# shield.net
KiCad netlist of a schematic drawn in EAGLE
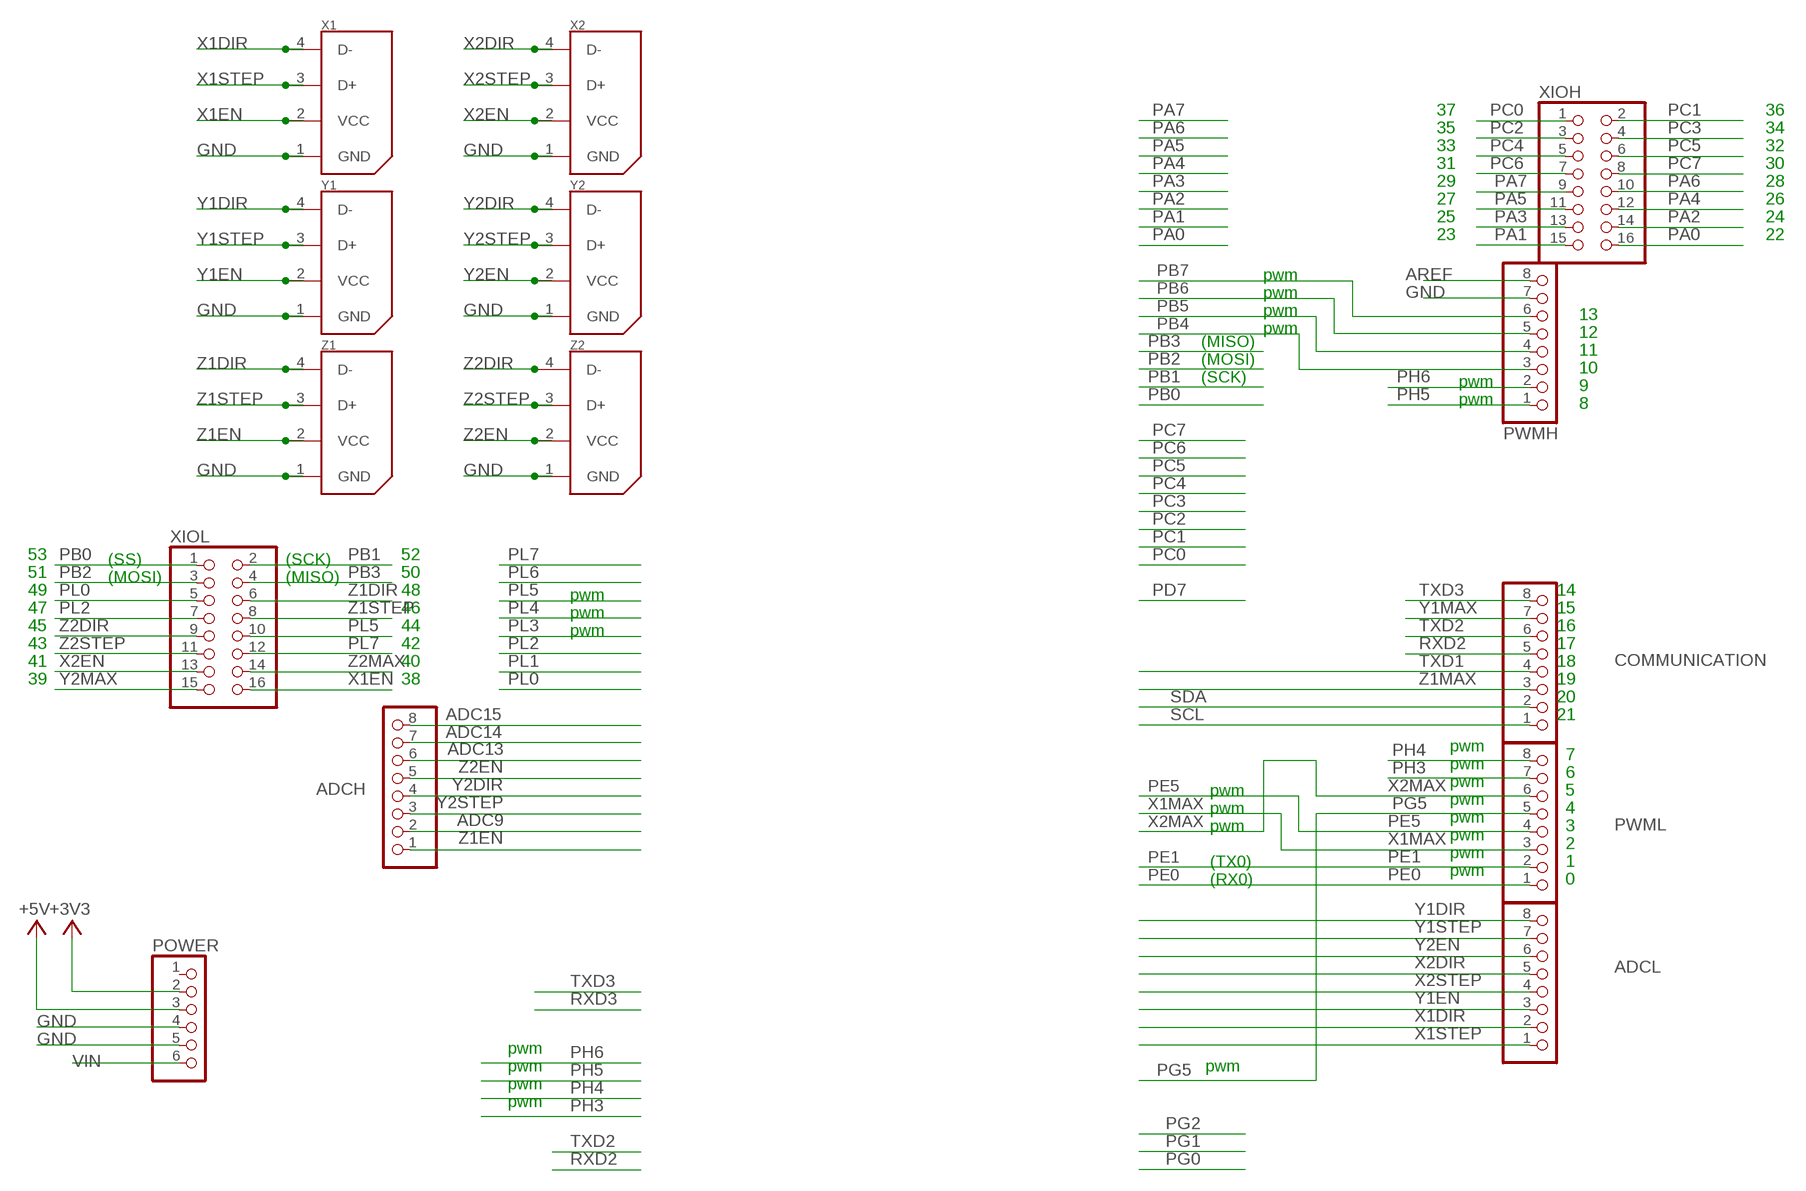
[diagram p0: schematic, sheet 1]

(export (version "E")
  (design (tool "Eeschema 10.0.6"))
  (components
    (comp (ref "ADCH")
      (value "PINHD-1X8")
      (footprint "eagle-import:1X08")
      (libsource (lib "eagle-import") (part "PINHD-1X8"))
    )
    (comp (ref "ADCL")
      (value "PINHD-1X8")
      (footprint "eagle-import:1X08")
      (libsource (lib "eagle-import") (part "PINHD-1X8"))
    )
    (comp (ref "COMMUNICATION")
      (value "PINHD-1X8")
      (footprint "eagle-import:1X08")
      (libsource (lib "eagle-import") (part "PINHD-1X8"))
    )
    (comp (ref "POWER")
      (value "PINHD-1X6")
      (footprint "eagle-import:1X06")
      (libsource (lib "eagle-import") (part "PINHD-1X6"))
    )
    (comp (ref "PWMH")
      (value "PINHD-1X8")
      (footprint "eagle-import:1X08")
      (libsource (lib "eagle-import") (part "PINHD-1X8"))
    )
    (comp (ref "PWML")
      (value "PINHD-1X8")
      (footprint "eagle-import:1X08")
      (libsource (lib "eagle-import") (part "PINHD-1X8"))
    )
    (comp (ref "X1")
      (value "22-03-5045")
      (footprint "eagle-import:5267-4")
      (libsource (lib "eagle-import") (part "22-03-5045"))
    )
    (comp (ref "X2")
      (value "22-03-5045")
      (footprint "eagle-import:5267-4")
      (libsource (lib "eagle-import") (part "22-03-5045"))
    )
    (comp (ref "XIOH")
      (value "PINHD-2X8")
      (footprint "eagle-import:2X08")
      (libsource (lib "eagle-import") (part "PINHD-2X8"))
    )
    (comp (ref "XIOL")
      (value "PINHD-2X8")
      (footprint "eagle-import:2X08")
      (libsource (lib "eagle-import") (part "PINHD-2X8"))
    )
    (comp (ref "Y1")
      (value "22-03-5045")
      (footprint "eagle-import:5267-4")
      (libsource (lib "eagle-import") (part "22-03-5045"))
    )
    (comp (ref "Y2")
      (value "22-03-5045")
      (footprint "eagle-import:5267-4")
      (libsource (lib "eagle-import") (part "22-03-5045"))
    )
    (comp (ref "Z1")
      (value "22-03-5045")
      (footprint "eagle-import:5267-4")
      (libsource (lib "eagle-import") (part "22-03-5045"))
    )
    (comp (ref "Z2")
      (value "22-03-5045")
      (footprint "eagle-import:5267-4")
      (libsource (lib "eagle-import") (part "22-03-5045"))
    )
  )
  (nets
    (net (code "1") (name "+3V3") (class "Default")
      (node (ref "POWER") (pin "2") (pinfunction "2_2") (pintype "passive"))
    )
    (net (code "2") (name "+5V") (class "Default")
      (node (ref "POWER") (pin "3") (pinfunction "3_3") (pintype "passive"))
    )
    (net (code "3") (name "/ADC9") (class "Default")
      (node (ref "ADCH") (pin "2") (pinfunction "2_2") (pintype "passive"))
    )
    (net (code "4") (name "/ADC13") (class "Default")
      (node (ref "ADCH") (pin "6") (pinfunction "6_6") (pintype "passive"))
    )
    (net (code "5") (name "/ADC14") (class "Default")
      (node (ref "ADCH") (pin "7") (pinfunction "7_7") (pintype "passive"))
    )
    (net (code "6") (name "/ADC15") (class "Default")
      (node (ref "ADCH") (pin "8") (pinfunction "8_8") (pintype "passive"))
    )
    (net (code "7") (name "/AREF") (class "Default")
      (node (ref "PWMH") (pin "8") (pinfunction "8_8") (pintype "passive"))
    )
    (net (code "8") (name "/GND") (class "Default")
      (node (ref "POWER") (pin "4") (pinfunction "4_4") (pintype "passive"))
      (node (ref "POWER") (pin "5") (pinfunction "5_5") (pintype "passive"))
      (node (ref "PWMH") (pin "7") (pinfunction "7_7") (pintype "passive"))
      (node (ref "X1") (pin "1") (pinfunction "GND_1") (pintype "bidirectional"))
      (node (ref "X2") (pin "1") (pinfunction "GND_1") (pintype "bidirectional"))
      (node (ref "Y1") (pin "1") (pinfunction "GND_1") (pintype "bidirectional"))
      (node (ref "Y2") (pin "1") (pinfunction "GND_1") (pintype "bidirectional"))
      (node (ref "Z1") (pin "1") (pinfunction "GND_1") (pintype "bidirectional"))
      (node (ref "Z2") (pin "1") (pinfunction "GND_1") (pintype "bidirectional"))
    )
    (net (code "9") (name "/PA0") (class "Default")
      (node (ref "XIOH") (pin "16") (pinfunction "16_16") (pintype "passive"))
    )
    (net (code "10") (name "/PA1") (class "Default")
      (node (ref "XIOH") (pin "15") (pinfunction "15_15") (pintype "passive"))
    )
    (net (code "11") (name "/PA2") (class "Default")
      (node (ref "XIOH") (pin "14") (pinfunction "14_14") (pintype "passive"))
    )
    (net (code "12") (name "/PA3") (class "Default")
      (node (ref "XIOH") (pin "13") (pinfunction "13_13") (pintype "passive"))
    )
    (net (code "13") (name "/PA4") (class "Default")
      (node (ref "XIOH") (pin "12") (pinfunction "12_12") (pintype "passive"))
    )
    (net (code "14") (name "/PA5") (class "Default")
      (node (ref "XIOH") (pin "11") (pinfunction "11_11") (pintype "passive"))
    )
    (net (code "15") (name "/PA6") (class "Default")
      (node (ref "XIOH") (pin "10") (pinfunction "10_10") (pintype "passive"))
    )
    (net (code "16") (name "/PA7") (class "Default")
      (node (ref "XIOH") (pin "9") (pinfunction "9_9") (pintype "passive"))
    )
    (net (code "17") (name "/PB0") (class "Default")
      (node (ref "XIOL") (pin "1") (pinfunction "1_1") (pintype "passive"))
    )
    (net (code "18") (name "/PB1") (class "Default")
      (node (ref "XIOL") (pin "2") (pinfunction "2_2") (pintype "passive"))
    )
    (net (code "19") (name "/PB2") (class "Default")
      (node (ref "XIOL") (pin "3") (pinfunction "3_3") (pintype "passive"))
    )
    (net (code "20") (name "/PB3") (class "Default")
      (node (ref "XIOL") (pin "4") (pinfunction "4_4") (pintype "passive"))
    )
    (net (code "21") (name "/PB4") (class "Default")
      (node (ref "PWMH") (pin "3") (pinfunction "3_3") (pintype "passive"))
    )
    (net (code "22") (name "/PB5") (class "Default")
      (node (ref "PWMH") (pin "4") (pinfunction "4_4") (pintype "passive"))
    )
    (net (code "23") (name "/PB6") (class "Default")
      (node (ref "PWMH") (pin "5") (pinfunction "5_5") (pintype "passive"))
    )
    (net (code "24") (name "/PB7") (class "Default")
      (node (ref "PWMH") (pin "6") (pinfunction "6_6") (pintype "passive"))
    )
    (net (code "25") (name "/PC0") (class "Default")
      (node (ref "XIOH") (pin "1") (pinfunction "1_1") (pintype "passive"))
    )
    (net (code "26") (name "/PC1") (class "Default")
      (node (ref "XIOH") (pin "2") (pinfunction "2_2") (pintype "passive"))
    )
    (net (code "27") (name "/PC2") (class "Default")
      (node (ref "XIOH") (pin "3") (pinfunction "3_3") (pintype "passive"))
    )
    (net (code "28") (name "/PC3") (class "Default")
      (node (ref "XIOH") (pin "4") (pinfunction "4_4") (pintype "passive"))
    )
    (net (code "29") (name "/PC4") (class "Default")
      (node (ref "XIOH") (pin "5") (pinfunction "5_5") (pintype "passive"))
    )
    (net (code "30") (name "/PC5") (class "Default")
      (node (ref "XIOH") (pin "6") (pinfunction "6_6") (pintype "passive"))
    )
    (net (code "31") (name "/PC6") (class "Default")
      (node (ref "XIOH") (pin "7") (pinfunction "7_7") (pintype "passive"))
    )
    (net (code "32") (name "/PC7") (class "Default")
      (node (ref "XIOH") (pin "8") (pinfunction "8_8") (pintype "passive"))
    )
    (net (code "34") (name "/PE0") (class "Default")
      (node (ref "PWML") (pin "1") (pinfunction "1_1") (pintype "passive"))
    )
    (net (code "35") (name "/PE1") (class "Default")
      (node (ref "PWML") (pin "2") (pinfunction "2_2") (pintype "passive"))
    )
    (net (code "36") (name "/PE5") (class "Default")
      (node (ref "PWML") (pin "4") (pinfunction "4_4") (pintype "passive"))
    )
    (net (code "40") (name "/PG5") (class "Default")
      (node (ref "PWML") (pin "5") (pinfunction "5_5") (pintype "passive"))
    )
    (net (code "41") (name "/PH3") (class "Default")
      (node (ref "PWML") (pin "7") (pinfunction "7_7") (pintype "passive"))
    )
    (net (code "42") (name "/PH4") (class "Default")
      (node (ref "PWML") (pin "8") (pinfunction "8_8") (pintype "passive"))
    )
    (net (code "43") (name "/PH5") (class "Default")
      (node (ref "PWMH") (pin "1") (pinfunction "1_1") (pintype "passive"))
    )
    (net (code "44") (name "/PH6") (class "Default")
      (node (ref "PWMH") (pin "2") (pinfunction "2_2") (pintype "passive"))
    )
    (net (code "45") (name "/PL0") (class "Default")
      (node (ref "XIOL") (pin "5") (pinfunction "5_5") (pintype "passive"))
    )
    (net (code "47") (name "/PL2") (class "Default")
      (node (ref "XIOL") (pin "7") (pinfunction "7_7") (pintype "passive"))
    )
    (net (code "50") (name "/PL5") (class "Default")
      (node (ref "XIOL") (pin "10") (pinfunction "10_10") (pintype "passive"))
    )
    (net (code "52") (name "/PL7") (class "Default")
      (node (ref "XIOL") (pin "12") (pinfunction "12_12") (pintype "passive"))
    )
    (net (code "53") (name "/RXD2") (class "Default")
      (node (ref "COMMUNICATION") (pin "5") (pinfunction "5_5") (pintype "passive"))
    )
    (net (code "55") (name "/SCL") (class "Default")
      (node (ref "COMMUNICATION") (pin "1") (pinfunction "1_1") (pintype "passive"))
    )
    (net (code "56") (name "/SDA") (class "Default")
      (node (ref "COMMUNICATION") (pin "2") (pinfunction "2_2") (pintype "passive"))
    )
    (net (code "57") (name "/TXD1") (class "Default")
      (node (ref "COMMUNICATION") (pin "4") (pinfunction "4_4") (pintype "passive"))
    )
    (net (code "58") (name "/TXD2") (class "Default")
      (node (ref "COMMUNICATION") (pin "6") (pinfunction "6_6") (pintype "passive"))
    )
    (net (code "59") (name "/TXD3") (class "Default")
      (node (ref "COMMUNICATION") (pin "8") (pinfunction "8_8") (pintype "passive"))
    )
    (net (code "60") (name "/VIN") (class "Default")
      (node (ref "POWER") (pin "6") (pinfunction "6_6") (pintype "passive"))
    )
    (net (code "61") (name "/X1DIR") (class "Default")
      (node (ref "ADCL") (pin "2") (pinfunction "2_2") (pintype "passive"))
      (node (ref "X1") (pin "4") (pinfunction "D-_4") (pintype "bidirectional"))
    )
    (net (code "62") (name "/X1EN") (class "Default")
      (node (ref "X1") (pin "2") (pinfunction "VCC_2") (pintype "bidirectional"))
      (node (ref "XIOL") (pin "16") (pinfunction "16_16") (pintype "passive"))
    )
    (net (code "63") (name "/X1MAX") (class "Default")
      (node (ref "PWML") (pin "3") (pinfunction "3_3") (pintype "passive"))
    )
    (net (code "64") (name "/X1STEP") (class "Default")
      (node (ref "ADCL") (pin "1") (pinfunction "1_1") (pintype "passive"))
      (node (ref "X1") (pin "3") (pinfunction "D+_3") (pintype "bidirectional"))
    )
    (net (code "65") (name "/X2DIR") (class "Default")
      (node (ref "ADCL") (pin "5") (pinfunction "5_5") (pintype "passive"))
      (node (ref "X2") (pin "4") (pinfunction "D-_4") (pintype "bidirectional"))
    )
    (net (code "66") (name "/X2EN") (class "Default")
      (node (ref "X2") (pin "2") (pinfunction "VCC_2") (pintype "bidirectional"))
      (node (ref "XIOL") (pin "13") (pinfunction "13_13") (pintype "passive"))
    )
    (net (code "67") (name "/X2MAX") (class "Default")
      (node (ref "PWML") (pin "6") (pinfunction "6_6") (pintype "passive"))
    )
    (net (code "68") (name "/X2STEP") (class "Default")
      (node (ref "ADCL") (pin "4") (pinfunction "4_4") (pintype "passive"))
      (node (ref "X2") (pin "3") (pinfunction "D+_3") (pintype "bidirectional"))
    )
    (net (code "69") (name "/Y1DIR") (class "Default")
      (node (ref "ADCL") (pin "8") (pinfunction "8_8") (pintype "passive"))
      (node (ref "Y1") (pin "4") (pinfunction "D-_4") (pintype "bidirectional"))
    )
    (net (code "70") (name "/Y1EN") (class "Default")
      (node (ref "ADCL") (pin "3") (pinfunction "3_3") (pintype "passive"))
      (node (ref "Y1") (pin "2") (pinfunction "VCC_2") (pintype "bidirectional"))
    )
    (net (code "71") (name "/Y1MAX") (class "Default")
      (node (ref "COMMUNICATION") (pin "7") (pinfunction "7_7") (pintype "passive"))
    )
    (net (code "72") (name "/Y1STEP") (class "Default")
      (node (ref "ADCL") (pin "7") (pinfunction "7_7") (pintype "passive"))
      (node (ref "Y1") (pin "3") (pinfunction "D+_3") (pintype "bidirectional"))
    )
    (net (code "73") (name "/Y2DIR") (class "Default")
      (node (ref "ADCH") (pin "4") (pinfunction "4_4") (pintype "passive"))
      (node (ref "Y2") (pin "4") (pinfunction "D-_4") (pintype "bidirectional"))
    )
    (net (code "74") (name "/Y2EN") (class "Default")
      (node (ref "ADCL") (pin "6") (pinfunction "6_6") (pintype "passive"))
      (node (ref "Y2") (pin "2") (pinfunction "VCC_2") (pintype "bidirectional"))
    )
    (net (code "75") (name "/Y2MAX") (class "Default")
      (node (ref "XIOL") (pin "15") (pinfunction "15_15") (pintype "passive"))
    )
    (net (code "76") (name "/Y2STEP") (class "Default")
      (node (ref "ADCH") (pin "3") (pinfunction "3_3") (pintype "passive"))
      (node (ref "Y2") (pin "3") (pinfunction "D+_3") (pintype "bidirectional"))
    )
    (net (code "77") (name "/Z1DIR") (class "Default")
      (node (ref "XIOL") (pin "6") (pinfunction "6_6") (pintype "passive"))
      (node (ref "Z1") (pin "4") (pinfunction "D-_4") (pintype "bidirectional"))
    )
    (net (code "78") (name "/Z1EN") (class "Default")
      (node (ref "ADCH") (pin "1") (pinfunction "1_1") (pintype "passive"))
      (node (ref "Z1") (pin "2") (pinfunction "VCC_2") (pintype "bidirectional"))
    )
    (net (code "79") (name "/Z1MAX") (class "Default")
      (node (ref "COMMUNICATION") (pin "3") (pinfunction "3_3") (pintype "passive"))
    )
    (net (code "80") (name "/Z1STEP") (class "Default")
      (node (ref "XIOL") (pin "8") (pinfunction "8_8") (pintype "passive"))
      (node (ref "Z1") (pin "3") (pinfunction "D+_3") (pintype "bidirectional"))
    )
    (net (code "81") (name "/Z2DIR") (class "Default")
      (node (ref "XIOL") (pin "9") (pinfunction "9_9") (pintype "passive"))
      (node (ref "Z2") (pin "4") (pinfunction "D-_4") (pintype "bidirectional"))
    )
    (net (code "82") (name "/Z2EN") (class "Default")
      (node (ref "ADCH") (pin "5") (pinfunction "5_5") (pintype "passive"))
      (node (ref "Z2") (pin "2") (pinfunction "VCC_2") (pintype "bidirectional"))
    )
    (net (code "83") (name "/Z2MAX") (class "Default")
      (node (ref "XIOL") (pin "14") (pinfunction "14_14") (pintype "passive"))
    )
    (net (code "84") (name "/Z2STEP") (class "Default")
      (node (ref "XIOL") (pin "11") (pinfunction "11_11") (pintype "passive"))
      (node (ref "Z2") (pin "3") (pinfunction "D+_3") (pintype "bidirectional"))
    )
    (net (code "85") (name "unconnected-(POWER-Pad1)") (class "Default")
      (node (ref "POWER") (pin "1") (pinfunction "1_1") (pintype "passive"))
    )
  )
)
